# NB2DSK-SPK.net
KiCad netlist of a schematic drawn in Altium Designer
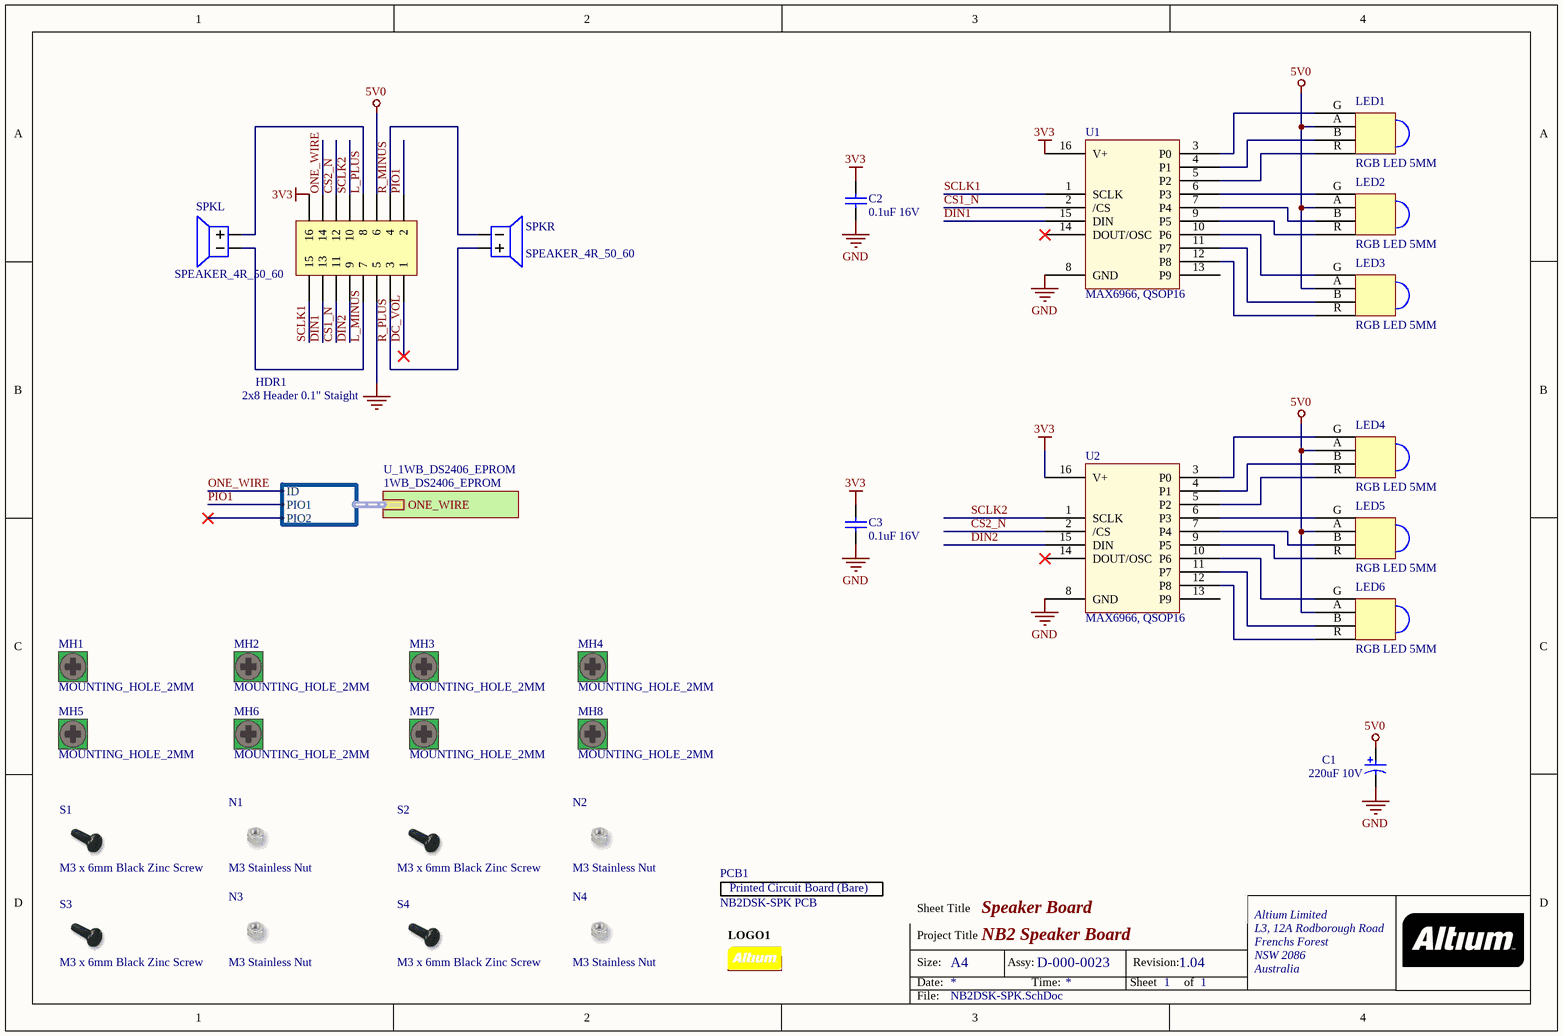
[diagram p0: NB2DSK-SPK.SchDoc]

(export (version "E")
  (design (tool "Eeschema 10.0.6"))
  (components
    (comp (ref "C1")
      (value "220uF 10V")
      (footprint "CAPC7343-STAR")
      (description "Capacitor, Tantalum, 220uF 10% 10V MCCT-D (7343-31)")
      (fields (field (name "TOLERANCE") "10 %"))
      (libsource (lib "AltiumDesignLibrary") (part "CAP-P"))
    )
    (comp (ref "C2")
      (value "0.1uF 16V")
      (footprint "CAPC1005-STAR")
      (description "Capacitor, Ceramic, 0.1uF 10% 16V 0402 (1005) X7R")
      (fields (field (name "TOLERANCE") "10 %"))
      (libsource (lib "AltiumDesignLibrary") (part "CAP-NP"))
    )
    (comp (ref "C3")
      (value "0.1uF 16V")
      (footprint "CAPC1005-STAR")
      (description "Capacitor, Ceramic, 0.1uF 10% 16V 0402 (1005) X7R")
      (fields (field (name "TOLERANCE") "10 %"))
      (libsource (lib "AltiumDesignLibrary") (part "CAP-NP"))
    )
    (comp (ref "HDR1")
      (value "2x8 Header 0.1\" Staight")
      (footprint "HDR2X8")
      (description "Header, BOX 2x8, 0.1\", Straight, Raised")
      (libsource (lib "AltiumDesignLibrary") (part "CON-HDR-2x8-STR"))
    )
    (comp (ref "LED1")
      (value "RGB LED 5MM")
      (footprint "LED-RGB-5MM-RA")
      (description "LED, RGB, 5mm, 540R2GBC-CA, Common Anode")
      (libsource (lib "AltiumDesignLibrary") (part "LED-RGB-5MM-RA"))
    )
    (comp (ref "LED2")
      (value "RGB LED 5MM")
      (footprint "LED-RGB-5MM-RA")
      (description "LED, RGB, 5mm, 540R2GBC-CA, Common Anode")
      (libsource (lib "AltiumDesignLibrary") (part "LED-RGB-5MM-RA"))
    )
    (comp (ref "LED3")
      (value "RGB LED 5MM")
      (footprint "LED-RGB-5MM-RA")
      (description "LED, RGB, 5mm, 540R2GBC-CA, Common Anode")
      (libsource (lib "AltiumDesignLibrary") (part "LED-RGB-5MM-RA"))
    )
    (comp (ref "LED4")
      (value "RGB LED 5MM")
      (footprint "LED-RGB-5MM-RA")
      (description "LED, RGB, 5mm, 540R2GBC-CA, Common Anode")
      (libsource (lib "AltiumDesignLibrary") (part "LED-RGB-5MM-RA"))
    )
    (comp (ref "LED5")
      (value "RGB LED 5MM")
      (footprint "LED-RGB-5MM-RA")
      (description "LED, RGB, 5mm, 540R2GBC-CA, Common Anode")
      (libsource (lib "AltiumDesignLibrary") (part "LED-RGB-5MM-RA"))
    )
    (comp (ref "LED6")
      (value "RGB LED 5MM")
      (footprint "LED-RGB-5MM-RA")
      (description "LED, RGB, 5mm, 540R2GBC-CA, Common Anode")
      (libsource (lib "AltiumDesignLibrary") (part "LED-RGB-5MM-RA"))
    )
    (comp (ref "LOGO1")
      (value "Altium")
      (footprint "Logo-Altium")
      (description "Altium Logo for PCB")
      (libsource (lib "altium-import") (part "root_0_Logo-Altium_"))
    )
    (comp (ref "MH1")
      (value "MOUNTING_HOLE_2MM")
      (footprint "MOUNTING_HOLE_2MM")
      (description "2mm Diameter Mounting Hole")
      (libsource (lib "Altium Design Library") (part "MOUNTING_HOLE_2MM"))
    )
    (comp (ref "MH2")
      (value "MOUNTING_HOLE_2MM")
      (footprint "MOUNTING_HOLE_2MM")
      (description "2mm Diameter Mounting Hole")
      (libsource (lib "Altium Design Library") (part "MOUNTING_HOLE_2MM"))
    )
    (comp (ref "MH3")
      (value "MOUNTING_HOLE_2MM")
      (footprint "MOUNTING_HOLE_2MM")
      (description "2mm Diameter Mounting Hole")
      (libsource (lib "Altium Design Library") (part "MOUNTING_HOLE_2MM"))
    )
    (comp (ref "MH4")
      (value "MOUNTING_HOLE_2MM")
      (footprint "MOUNTING_HOLE_2MM")
      (description "2mm Diameter Mounting Hole")
      (libsource (lib "Altium Design Library") (part "MOUNTING_HOLE_2MM"))
    )
    (comp (ref "MH5")
      (value "MOUNTING_HOLE_2MM")
      (footprint "MOUNTING_HOLE_2MM")
      (description "2mm Diameter Mounting Hole")
      (libsource (lib "Altium Design Library") (part "MOUNTING_HOLE_2MM"))
    )
    (comp (ref "MH6")
      (value "MOUNTING_HOLE_2MM")
      (footprint "MOUNTING_HOLE_2MM")
      (description "2mm Diameter Mounting Hole")
      (libsource (lib "Altium Design Library") (part "MOUNTING_HOLE_2MM"))
    )
    (comp (ref "MH7")
      (value "MOUNTING_HOLE_2MM")
      (footprint "MOUNTING_HOLE_2MM")
      (description "2mm Diameter Mounting Hole")
      (libsource (lib "Altium Design Library") (part "MOUNTING_HOLE_2MM"))
    )
    (comp (ref "MH8")
      (value "MOUNTING_HOLE_2MM")
      (footprint "MOUNTING_HOLE_2MM")
      (description "2mm Diameter Mounting Hole")
      (libsource (lib "Altium Design Library") (part "MOUNTING_HOLE_2MM"))
    )
    (comp (ref "N1")
      (value "M3 Stainless Nut")
      (libsource (lib "AltiumDesignLibrary") (part "SCREW-STAINLESS-NUT"))
    )
    (comp (ref "N2")
      (value "M3 Stainless Nut")
      (libsource (lib "AltiumDesignLibrary") (part "SCREW-STAINLESS-NUT"))
    )
    (comp (ref "N3")
      (value "M3 Stainless Nut")
      (libsource (lib "AltiumDesignLibrary") (part "SCREW-STAINLESS-NUT"))
    )
    (comp (ref "N4")
      (value "M3 Stainless Nut")
      (libsource (lib "AltiumDesignLibrary") (part "SCREW-STAINLESS-NUT"))
    )
    (comp (ref "PCB1")
      (value "NB2DSK-SPK PCB")
      (description "PCB, NB2 Speaker Board (NB2DSK-SPK)")
      (libsource (lib "AltiumDesignLibrary") (part "PCB-BARE"))
    )
    (comp (ref "S1")
      (value "M3 x 6mm Black Zinc Screw")
      (description "M3 Black-Zinc Cross-Recess Pan-Head Machine Screw 6mm long")
      (libsource (lib "AltiumDesignLibrary") (part "SCREW-BLACK"))
    )
    (comp (ref "S2")
      (value "M3 x 6mm Black Zinc Screw")
      (description "M3 Black-Zinc Cross-Recess Pan-Head Machine Screw 6mm long")
      (libsource (lib "AltiumDesignLibrary") (part "SCREW-BLACK"))
    )
    (comp (ref "S3")
      (value "M3 x 6mm Black Zinc Screw")
      (description "M3 Black-Zinc Cross-Recess Pan-Head Machine Screw 6mm long")
      (libsource (lib "AltiumDesignLibrary") (part "SCREW-BLACK"))
    )
    (comp (ref "S4")
      (value "M3 x 6mm Black Zinc Screw")
      (description "M3 Black-Zinc Cross-Recess Pan-Head Machine Screw 6mm long")
      (libsource (lib "AltiumDesignLibrary") (part "SCREW-BLACK"))
    )
    (comp (ref "SPKL")
      (value "SPEAKER_4R_50_60")
      (footprint "SPEAKER_4R_50_60")
      (description "Speaker, 4 Omh 3W 50mm Cone 60mm Body")
      (libsource (lib "AltiumDesignLibrary") (part "SPEAKER_POL"))
    )
    (comp (ref "SPKR")
      (value "SPEAKER_4R_50_60")
      (footprint "SPEAKER_4R_50_60")
      (description "Speaker, 4 Omh 3W 50mm Cone 60mm Body")
      (libsource (lib "AltiumDesignLibrary") (part "SPEAKER_POL"))
    )
    (comp (ref "U1")
      (value "MAX6966, QSOP16")
      (footprint "QSOP16")
      (description "MAX6966, 10 port Constant Current LED Driver, SPI")
      (libsource (lib "AltiumDesignLibrary") (part "MAX6966"))
    )
    (comp (ref "U2")
      (value "MAX6966, QSOP16")
      (footprint "QSOP16")
      (description "MAX6966, 10 port Constant Current LED Driver, SPI")
      (libsource (lib "AltiumDesignLibrary") (part "MAX6966"))
    )
  )
  (nets
    (net (code "1") (name "/CS1_N") (class "Default")
      (node (ref "HDR1") (pin "11") (pinfunction "11_11") (pintype "passive"))
      (node (ref "U1") (pin "2") (pinfunction "/CS_2") (pintype "passive"))
    )
    (net (code "2") (name "/CS2_N") (class "Default")
      (node (ref "HDR1") (pin "12") (pinfunction "12_12") (pintype "passive"))
      (node (ref "U2") (pin "2") (pinfunction "/CS_2") (pintype "passive"))
    )
    (net (code "3") (name "/DC_VOL") (class "Default")
      (node (ref "HDR1") (pin "1") (pinfunction "1_1") (pintype "passive+no_connect"))
    )
    (net (code "4") (name "/DIN1") (class "Default")
      (node (ref "HDR1") (pin "13") (pinfunction "13_13") (pintype "passive"))
      (node (ref "U1") (pin "15") (pinfunction "DIN_15") (pintype "passive"))
    )
    (net (code "5") (name "/DIN2") (class "Default")
      (node (ref "HDR1") (pin "9") (pinfunction "9_9") (pintype "passive"))
      (node (ref "U2") (pin "15") (pinfunction "DIN_15") (pintype "passive"))
    )
    (net (code "6") (name "/L_MINUS") (class "Default")
      (node (ref "HDR1") (pin "7") (pinfunction "7_7") (pintype "passive"))
      (node (ref "SPKL") (pin "2") (pintype "passive"))
    )
    (net (code "7") (name "/L_PLUS") (class "Default")
      (node (ref "HDR1") (pin "8") (pinfunction "8_8") (pintype "passive"))
      (node (ref "SPKL") (pin "1") (pintype "passive"))
    )
    (net (code "8") (name "/ONE_WIRE") (class "Default")
      (node (ref "HDR1") (pin "14") (pinfunction "14_14") (pintype "passive"))
    )
    (net (code "9") (name "/PIO1") (class "Default")
      (node (ref "HDR1") (pin "2") (pinfunction "2_2") (pintype "passive"))
    )
    (net (code "10") (name "/R_MINUS") (class "Default")
      (node (ref "HDR1") (pin "4") (pinfunction "4_4") (pintype "passive"))
      (node (ref "SPKR") (pin "2") (pintype "passive"))
    )
    (net (code "11") (name "/R_PLUS") (class "Default")
      (node (ref "HDR1") (pin "3") (pinfunction "3_3") (pintype "passive"))
      (node (ref "SPKR") (pin "1") (pintype "passive"))
    )
    (net (code "12") (name "/SCLK1") (class "Default")
      (node (ref "HDR1") (pin "15") (pinfunction "15_15") (pintype "passive"))
      (node (ref "U1") (pin "1") (pinfunction "SCLK_1") (pintype "passive"))
    )
    (net (code "13") (name "/SCLK2") (class "Default")
      (node (ref "HDR1") (pin "10") (pinfunction "10_10") (pintype "passive"))
      (node (ref "U2") (pin "1") (pinfunction "SCLK_1") (pintype "passive"))
    )
    (net (code "15") (name "3V3") (class "Default")
      (node (ref "C2") (pin "2") (pinfunction "2_2") (pintype "passive"))
      (node (ref "C3") (pin "2") (pinfunction "2_2") (pintype "passive"))
      (node (ref "HDR1") (pin "16") (pinfunction "16_16") (pintype "passive"))
      (node (ref "U1") (pin "16") (pinfunction "V+_16") (pintype "passive"))
      (node (ref "U2") (pin "16") (pinfunction "V+_16") (pintype "passive"))
    )
    (net (code "16") (name "5V0") (class "Default")
      (node (ref "C1") (pin "1") (pinfunction "1_1") (pintype "passive"))
      (node (ref "HDR1") (pin "6") (pinfunction "6_6") (pintype "passive"))
      (node (ref "LED1") (pin "A") (pinfunction "A_A") (pintype "passive"))
      (node (ref "LED2") (pin "A") (pinfunction "A_A") (pintype "passive"))
      (node (ref "LED3") (pin "A") (pinfunction "A_A") (pintype "passive"))
      (node (ref "LED4") (pin "A") (pinfunction "A_A") (pintype "passive"))
      (node (ref "LED5") (pin "A") (pinfunction "A_A") (pintype "passive"))
      (node (ref "LED6") (pin "A") (pinfunction "A_A") (pintype "passive"))
    )
    (net (code "17") (name "GND") (class "Default")
      (node (ref "C1") (pin "2") (pinfunction "2_2") (pintype "passive"))
      (node (ref "C2") (pin "1") (pinfunction "1_1") (pintype "passive"))
      (node (ref "C3") (pin "1") (pinfunction "1_1") (pintype "passive"))
      (node (ref "HDR1") (pin "5") (pinfunction "5_5") (pintype "passive"))
      (node (ref "U1") (pin "8") (pinfunction "GND_8") (pintype "passive"))
      (node (ref "U2") (pin "8") (pinfunction "GND_8") (pintype "passive"))
    )
    (net (code "18") (name "Net-(U1-P0)") (class "Default")
      (node (ref "LED1") (pin "G") (pinfunction "G_G") (pintype "passive"))
      (node (ref "U1") (pin "3") (pinfunction "P0_3") (pintype "passive"))
    )
    (net (code "19") (name "Net-(U1-P1)") (class "Default")
      (node (ref "LED1") (pin "B") (pinfunction "B_B") (pintype "passive"))
      (node (ref "U1") (pin "4") (pinfunction "P1_4") (pintype "passive"))
    )
    (net (code "20") (name "Net-(U1-P2)") (class "Default")
      (node (ref "LED1") (pin "R") (pinfunction "R_R") (pintype "passive"))
      (node (ref "U1") (pin "5") (pinfunction "P2_5") (pintype "passive"))
    )
    (net (code "21") (name "Net-(U1-P3)") (class "Default")
      (node (ref "LED2") (pin "G") (pinfunction "G_G") (pintype "passive"))
      (node (ref "U1") (pin "6") (pinfunction "P3_6") (pintype "passive"))
    )
    (net (code "22") (name "Net-(U1-P4)") (class "Default")
      (node (ref "LED2") (pin "B") (pinfunction "B_B") (pintype "passive"))
      (node (ref "U1") (pin "7") (pinfunction "P4_7") (pintype "passive"))
    )
    (net (code "23") (name "Net-(U1-P5)") (class "Default")
      (node (ref "LED2") (pin "R") (pinfunction "R_R") (pintype "passive"))
      (node (ref "U1") (pin "9") (pinfunction "P5_9") (pintype "passive"))
    )
    (net (code "24") (name "Net-(U1-P6)") (class "Default")
      (node (ref "LED3") (pin "G") (pinfunction "G_G") (pintype "passive"))
      (node (ref "U1") (pin "10") (pinfunction "P6_10") (pintype "passive"))
    )
    (net (code "25") (name "Net-(U1-P7)") (class "Default")
      (node (ref "LED3") (pin "B") (pinfunction "B_B") (pintype "passive"))
      (node (ref "U1") (pin "11") (pinfunction "P7_11") (pintype "passive"))
    )
    (net (code "26") (name "Net-(U1-P8)") (class "Default")
      (node (ref "LED3") (pin "R") (pinfunction "R_R") (pintype "passive"))
      (node (ref "U1") (pin "12") (pinfunction "P8_12") (pintype "passive"))
    )
    (net (code "27") (name "Net-(U2-P0)") (class "Default")
      (node (ref "LED4") (pin "G") (pinfunction "G_G") (pintype "passive"))
      (node (ref "U2") (pin "3") (pinfunction "P0_3") (pintype "passive"))
    )
    (net (code "28") (name "Net-(U2-P1)") (class "Default")
      (node (ref "LED4") (pin "B") (pinfunction "B_B") (pintype "passive"))
      (node (ref "U2") (pin "4") (pinfunction "P1_4") (pintype "passive"))
    )
    (net (code "29") (name "Net-(U2-P2)") (class "Default")
      (node (ref "LED4") (pin "R") (pinfunction "R_R") (pintype "passive"))
      (node (ref "U2") (pin "5") (pinfunction "P2_5") (pintype "passive"))
    )
    (net (code "30") (name "Net-(U2-P3)") (class "Default")
      (node (ref "LED5") (pin "G") (pinfunction "G_G") (pintype "passive"))
      (node (ref "U2") (pin "6") (pinfunction "P3_6") (pintype "passive"))
    )
    (net (code "31") (name "Net-(U2-P4)") (class "Default")
      (node (ref "LED5") (pin "B") (pinfunction "B_B") (pintype "passive"))
      (node (ref "U2") (pin "7") (pinfunction "P4_7") (pintype "passive"))
    )
    (net (code "32") (name "Net-(U2-P5)") (class "Default")
      (node (ref "LED5") (pin "R") (pinfunction "R_R") (pintype "passive"))
      (node (ref "U2") (pin "9") (pinfunction "P5_9") (pintype "passive"))
    )
    (net (code "33") (name "Net-(U2-P6)") (class "Default")
      (node (ref "LED6") (pin "G") (pinfunction "G_G") (pintype "passive"))
      (node (ref "U2") (pin "10") (pinfunction "P6_10") (pintype "passive"))
    )
    (net (code "34") (name "Net-(U2-P7)") (class "Default")
      (node (ref "LED6") (pin "B") (pinfunction "B_B") (pintype "passive"))
      (node (ref "U2") (pin "11") (pinfunction "P7_11") (pintype "passive"))
    )
    (net (code "35") (name "Net-(U2-P8)") (class "Default")
      (node (ref "LED6") (pin "R") (pinfunction "R_R") (pintype "passive"))
      (node (ref "U2") (pin "12") (pinfunction "P8_12") (pintype "passive"))
    )
    (net (code "36") (name "unconnected-(MH1-Pad1)") (class "Default")
      (node (ref "MH1") (pin "1") (pinfunction "1_1") (pintype "passive"))
    )
    (net (code "37") (name "unconnected-(MH2-Pad1)") (class "Default")
      (node (ref "MH2") (pin "1") (pinfunction "1_1") (pintype "passive"))
    )
    (net (code "38") (name "unconnected-(MH3-Pad1)") (class "Default")
      (node (ref "MH3") (pin "1") (pinfunction "1_1") (pintype "passive"))
    )
    (net (code "39") (name "unconnected-(MH4-Pad1)") (class "Default")
      (node (ref "MH4") (pin "1") (pinfunction "1_1") (pintype "passive"))
    )
    (net (code "40") (name "unconnected-(MH5-Pad1)") (class "Default")
      (node (ref "MH5") (pin "1") (pinfunction "1_1") (pintype "passive"))
    )
    (net (code "41") (name "unconnected-(MH6-Pad1)") (class "Default")
      (node (ref "MH6") (pin "1") (pinfunction "1_1") (pintype "passive"))
    )
    (net (code "42") (name "unconnected-(MH7-Pad1)") (class "Default")
      (node (ref "MH7") (pin "1") (pinfunction "1_1") (pintype "passive"))
    )
    (net (code "43") (name "unconnected-(MH8-Pad1)") (class "Default")
      (node (ref "MH8") (pin "1") (pinfunction "1_1") (pintype "passive"))
    )
    (net (code "44") (name "unconnected-(U1-DOUT{slash}OSC-Pad14)") (class "Default")
      (node (ref "U1") (pin "14") (pinfunction "DOUT/OSC_14") (pintype "passive+no_connect"))
    )
    (net (code "45") (name "unconnected-(U1-P9-Pad13)") (class "Default")
      (node (ref "U1") (pin "13") (pinfunction "P9_13") (pintype "passive"))
    )
    (net (code "46") (name "unconnected-(U2-DOUT{slash}OSC-Pad14)") (class "Default")
      (node (ref "U2") (pin "14") (pinfunction "DOUT/OSC_14") (pintype "passive+no_connect"))
    )
    (net (code "47") (name "unconnected-(U2-P9-Pad13)") (class "Default")
      (node (ref "U2") (pin "13") (pinfunction "P9_13") (pintype "passive"))
    )
  )
)
